# Power.net
KiCad netlist of a schematic drawn in Altium Designer
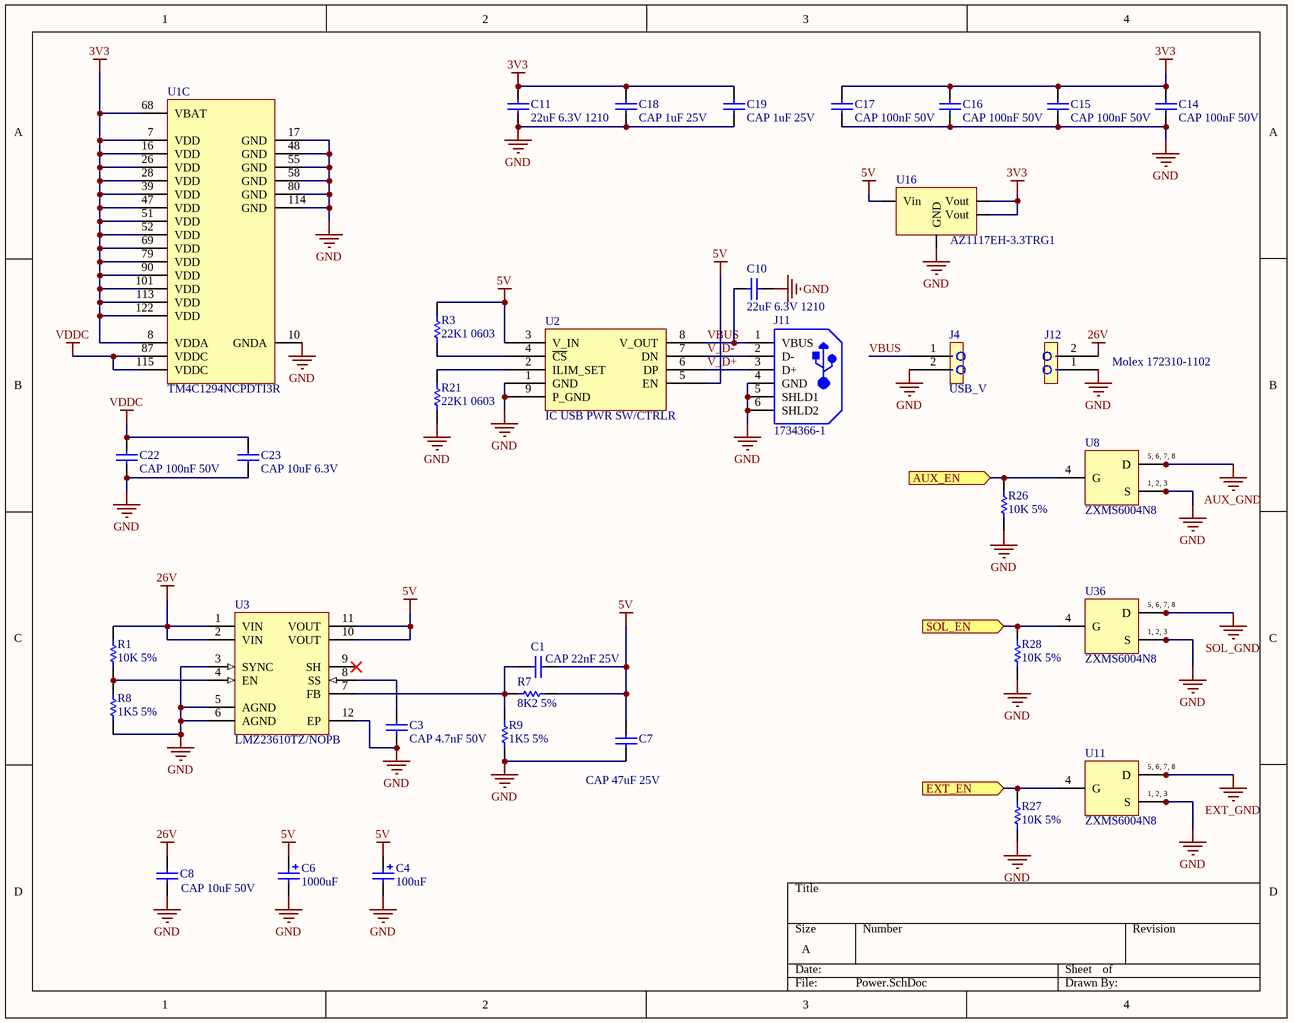
[diagram p0: Power.SchDoc]

(export (version "E")
  (design (tool "Eeschema 10.0.6"))
  (components
    (comp (ref "C1")
      (value "CAP 22nF 25V")
      (footprint "CAPC0805(2012)100_M")
      (description "CAP 22nF 25V Â±5% 0805 (2012 Metric) Thickness 1mm SMD")
      (fields (field (name "TOLERANCE") "Â±5%"))
      (libsource (lib "Altium Content Vault") (part "CMP-1036-04051-1"))
    )
    (comp (ref "C3")
      (value "CAP 4.7nF 50V")
      (footprint "CAPC0603(1608)100_M")
      (description "CAP 4.7nF 50V Â±20% 0603 (1608 Metric) Thickness 1mm SMD")
      (fields (field (name "TOLERANCE") "Â±20%"))
      (libsource (lib "Altium Content Vault") (part "CMP-1035-00333-1"))
    )
    (comp (ref "C4")
      (value "100uF")
      (footprint "PANASONIC_C")
      (description "Polarized Capacitor (Surface Mount)")
      (fields (field (name "PUBLISHER") "Altium Limited"))
      (libsource (lib "snarc+") (part "Cap_Polarized_100uF"))
    )
    (comp (ref "C6")
      (value "1000uF")
      (footprint "PANASONIC_H13")
      (description "Polarized Capacitor (Surface Mount)")
      (fields (field (name "PUBLISHER") "Altium Limited"))
      (libsource (lib "snarc+") (part "Cap_Polarized_1000uF"))
    )
    (comp (ref "C7")
      (value "CAP 47uF 25V")
      (footprint "CAPC1206(3216)100_L")
      (description "CAP 47uF 25V Â±0.25pF 1206 (3216 Metric) Thickness 1mm SMD")
      (fields (field (name "TOLERANCE") "Â±0.25pF"))
      (libsource (lib "Altium Content Vault") (part "CMP-1037-00376-1"))
    )
    (comp (ref "C8")
      (value "CAP 10uF 50V")
      (footprint "CAPC1206(3216)190_M")
      (description "CAP 10uF 50V Â±10% 1206 (3216 Metric) Thickness 1.9mm SMD")
      (fields (field (name "TOLERANCE") "Â±10%"))
      (libsource (lib "Altium Content Vault") (part "CMP-1037-04982-1"))
    )
    (comp (ref "C10")
      (value "22uF 6.3V 1210")
      (footprint "CAPC1210(3225)220_N")
      (description "CAP 22uF 6.3V ±10% 1210 (3225 Metric) Thickness 2.2mm SMD")
      (fields (field (name "TOLERANCE") "Â±10%"))
      (libsource (lib "Altium Content Vault") (part "CAP"))
    )
    (comp (ref "C11")
      (value "22uF 6.3V 1210")
      (footprint "CAPC1210(3225)220_N")
      (description "CAP 22uF 6.3V ±10% 1210 (3225 Metric) Thickness 2.2mm SMD")
      (fields (field (name "TOLERANCE") "Â±10%"))
      (libsource (lib "Altium Content Vault") (part "CAP"))
    )
    (comp (ref "C14")
      (value "CAP 100nF 50V")
      (footprint "CAPC0603(1608)100_M")
      (description "CAP 100nF 50V Â±0.1pF 0603 (1608 Metric) Thickness 1mm SMD")
      (fields (field (name "TOLERANCE") "Â±0.1pF"))
      (libsource (lib "Altium Content Vault") (part "CMP-1035-00010-1"))
    )
    (comp (ref "C15")
      (value "CAP 100nF 50V")
      (footprint "CAPC0603(1608)100_M")
      (description "CAP 100nF 50V Â±0.1pF 0603 (1608 Metric) Thickness 1mm SMD")
      (fields (field (name "TOLERANCE") "Â±0.1pF"))
      (libsource (lib "Altium Content Vault") (part "CMP-1035-00010-1"))
    )
    (comp (ref "C16")
      (value "CAP 100nF 50V")
      (footprint "CAPC0603(1608)100_M")
      (description "CAP 100nF 50V Â±0.1pF 0603 (1608 Metric) Thickness 1mm SMD")
      (fields (field (name "TOLERANCE") "Â±0.1pF"))
      (libsource (lib "Altium Content Vault") (part "CMP-1035-00010-1"))
    )
    (comp (ref "C17")
      (value "CAP 100nF 50V")
      (footprint "CAPC0603(1608)100_M")
      (description "CAP 100nF 50V Â±0.1pF 0603 (1608 Metric) Thickness 1mm SMD")
      (fields (field (name "TOLERANCE") "Â±0.1pF"))
      (libsource (lib "Altium Content Vault") (part "CMP-1035-00010-1"))
    )
    (comp (ref "C18")
      (value "CAP 1uF 25V")
      (footprint "CAPC0603(1608)100_M")
      (description "CAP 1uF 25V Â±0.25pF 0603 (1608 Metric) Thickness 1mm SMD")
      (fields (field (name "TOLERANCE") "Â±0.25pF"))
      (libsource (lib "Altium Content Vault") (part "CMP-1035-00037-1"))
    )
    (comp (ref "C19")
      (value "CAP 1uF 25V")
      (footprint "CAPC0603(1608)100_M")
      (description "CAP 1uF 25V Â±0.25pF 0603 (1608 Metric) Thickness 1mm SMD")
      (fields (field (name "TOLERANCE") "Â±0.25pF"))
      (libsource (lib "Altium Content Vault") (part "CMP-1035-00037-1"))
    )
    (comp (ref "C22")
      (value "CAP 100nF 50V")
      (footprint "CAPC0603(1608)100_M")
      (description "CAP 100nF 50V Â±0.1pF 0603 (1608 Metric) Thickness 1mm SMD")
      (fields (field (name "TOLERANCE") "Â±0.1pF"))
      (libsource (lib "Altium Content Vault") (part "CMP-1035-00010-1"))
    )
    (comp (ref "C23")
      (value "CAP 10uF 6.3V")
      (footprint "CAPC0603(1608)100_M")
      (description "CAP 10uF 6.3V ±10% 0603 (1608 Metric) Thickness 1mm SMD")
      (fields (field (name "TOLERANCE") "Â±10%"))
      (libsource (lib "Altium Content Vault") (part "CMP-1035-02796-1"))
    )
    (comp (ref "J4")
      (value "USB_V")
      (footprint "1X2")
      (description "6.35mm right-angle 90° male spade terminal PCB mount")
      (libsource (lib "") (part "CON2_1"))
    )
    (comp (ref "J11")
      (value "1734366-1")
      (footprint "TE-1734366-1_V")
      (description "Recept Assy, Vertical, 4 Position, Thru-Hole, Type A USB, RoHS, Tray")
      (libsource (lib "Altium Content Vault") (part "USB-4-2SHLD"))
    )
    (comp (ref "J12")
      (value "Molex 172310-1102")
      (footprint "Molex 172310-1102")
      (description "6.35mm right-angle 90° male spade terminal PCB mount")
      (libsource (lib "HSBNE-Vend") (part "CON2"))
    )
    (comp (ref "R1")
      (value "10K 5%")
      (footprint "RESC0603(1608)_M")
      (description "10K 0.1W 5% 0603 (1608 Metric)  SMD")
      (fields (field (name "TOLERANCE") "5 %") (field (name "POWER") "0.1 W"))
      (libsource (lib "Altium Content Vault") (part "CMP-1012-00098-1"))
    )
    (comp (ref "R3")
      (value "22K1 0603")
      (footprint "RESC0603(1608)_N")
      (description "22K1 0.1W 1% 0603 (1608 Metric)  SMD")
      (fields (field (name "TOLERANCE") "1 %") (field (name "POWER") "0.1 W"))
      (libsource (lib "Altium Content Vault") (part "RES"))
    )
    (comp (ref "R7")
      (value "8K2 5%")
      (footprint "RESC0603(1608)_M")
      (description "8K2 0.1W 5% 0603 (1608 Metric)  SMD")
      (fields (field (name "TOLERANCE") "5 %") (field (name "POWER") "0.1 W"))
      (libsource (lib "Altium Content Vault") (part "CMP-1012-00096-1"))
    )
    (comp (ref "R8")
      (value "1K5 5%")
      (footprint "RESC0603(1608)_M")
      (description "1K5 0.1W 5% 0603 (1608 Metric)  SMD")
      (fields (field (name "POWER") "0.1 W") (field (name "TOLERANCE") "5 %"))
      (libsource (lib "Altium Content Vault") (part "CMP-1012-00078-1"))
    )
    (comp (ref "R9")
      (value "1K5 5%")
      (footprint "RESC0603(1608)_M")
      (description "1K5 0.1W 5% 0603 (1608 Metric)  SMD")
      (fields (field (name "POWER") "0.1 W") (field (name "TOLERANCE") "5 %"))
      (libsource (lib "Altium Content Vault") (part "CMP-1012-00078-1"))
    )
    (comp (ref "R21")
      (value "22K1 0603")
      (footprint "RESC0603(1608)_N")
      (description "22K1 0.1W 1% 0603 (1608 Metric)  SMD")
      (fields (field (name "TOLERANCE") "1 %") (field (name "POWER") "0.1 W"))
      (libsource (lib "Altium Content Vault") (part "RES"))
    )
    (comp (ref "R26")
      (value "10K 5%")
      (footprint "RESC0603(1608)_N")
      (description "10K 0.1W 5% 0603 (1608 Metric)  SMD")
      (fields (field (name "TOLERANCE") "5 %") (field (name "POWER") "0.1 W"))
      (libsource (lib "Altium Content Vault") (part "RES"))
    )
    (comp (ref "R27")
      (value "10K 5%")
      (footprint "RESC0603(1608)_N")
      (description "10K 0.1W 5% 0603 (1608 Metric)  SMD")
      (fields (field (name "TOLERANCE") "5 %") (field (name "POWER") "0.1 W"))
      (libsource (lib "Altium Content Vault") (part "RES"))
    )
    (comp (ref "R28")
      (value "10K 5%")
      (footprint "RESC0603(1608)_N")
      (description "10K 0.1W 5% 0603 (1608 Metric)  SMD")
      (fields (field (name "TOLERANCE") "5 %") (field (name "POWER") "0.1 W"))
      (libsource (lib "Altium Content Vault") (part "RES"))
    )
    (comp (ref "U1")
      (value "TM4C1294NCPDTI3R")
      (footprint "TI-PDT128_M")
      (fields (field (name "MANUFACTURER") "Texas Instruments"))
      (libsource (lib "Altium Inc") (part "TI-TM4C1294NCPDT-128"))
    )
    (comp (ref "U2")
      (value "IC USB PWR SW/CTRLR")
      (footprint "8-MSOP-PowerPad")
      (description "USB Dedicated Charging Port, Power Switch")
      (libsource (lib "HSBNE-Vend") (part "IC USB PWR SW/CTRLR"))
    )
    (comp (ref "U3")
      (value "LMZ23610TZ/NOPB")
      (footprint "NDY0011A_M")
      (fields (field (name "MANUFACTURER") "Texas Instruments"))
      (libsource (lib "Altium Content Vault") (part "PM-REG-LMZ23610-12"))
    )
    (comp (ref "U8")
      (value "ZXMS6004N8")
      (footprint "SO-8")
      (description "MOSFET N-CH 60V 1.3A S08")
      (fields (field (name "MANUFACTURER") "On Semiconductor") (field (name "PARTNUMBER") "NCV8402ASTT1G"))
      (libsource (lib "HSBNE-MAIN") (part "ZXMS6004N8"))
    )
    (comp (ref "U11")
      (value "ZXMS6004N8")
      (footprint "SO-8")
      (description "MOSFET N-CH 60V 1.3A S08")
      (fields (field (name "MANUFACTURER") "On Semiconductor") (field (name "PARTNUMBER") "NCV8402ASTT1G"))
      (libsource (lib "HSBNE-MAIN") (part "ZXMS6004N8"))
    )
    (comp (ref "U16")
      (value "AZ1117EH-3.3TRG1")
      (footprint "SOT-223")
      (description "Reg 1A 3V3 OUT SIP VERT")
      (libsource (lib "HSBNE-Vend") (part "AZ1117EH"))
    )
    (comp (ref "U36")
      (value "ZXMS6004N8")
      (footprint "SO-8")
      (description "MOSFET N-CH 60V 1.3A S08")
      (fields (field (name "MANUFACTURER") "On Semiconductor") (field (name "PARTNUMBER") "NCV8402ASTT1G"))
      (libsource (lib "HSBNE-MAIN") (part "ZXMS6004N8"))
    )
  )
  (nets
    (net (code "1") (name "/AUX_EN") (class "Default")
      (node (ref "R26") (pin "2") (pinfunction "2_2") (pintype "passive"))
      (node (ref "U8") (pin "4") (pinfunction "G_4") (pintype "passive"))
    )
    (net (code "2") (name "/EXT_EN") (class "Default")
      (node (ref "R27") (pin "2") (pinfunction "2_2") (pintype "passive"))
      (node (ref "U11") (pin "4") (pinfunction "G_4") (pintype "passive"))
    )
    (net (code "3") (name "/SOL_EN") (class "Default")
      (node (ref "R28") (pin "2") (pinfunction "2_2") (pintype "passive"))
      (node (ref "U36") (pin "4") (pinfunction "G_4") (pintype "passive"))
    )
    (net (code "4") (name "/VBUS") (class "Default")
      (node (ref "C10") (pin "1") (pinfunction "1_1") (pintype "passive"))
      (node (ref "J11") (pin "1") (pinfunction "VBUS_1") (pintype "passive"))
      (node (ref "J4") (pin "1") (pintype "passive"))
      (node (ref "U2") (pin "8") (pinfunction "V_OUT_8") (pintype "power_in"))
    )
    (net (code "5") (name "/V_D+") (class "Default")
      (node (ref "J11") (pin "3") (pinfunction "D+_3") (pintype "passive"))
      (node (ref "U2") (pin "6") (pinfunction "DP_6") (pintype "power_in"))
    )
    (net (code "6") (name "/V_D-") (class "Default")
      (node (ref "J11") (pin "2") (pinfunction "D-_2") (pintype "passive"))
      (node (ref "U2") (pin "7") (pinfunction "DN_7") (pintype "power_in"))
    )
    (net (code "7") (name "3V3") (class "Default")
      (node (ref "C11") (pin "2") (pinfunction "2_2") (pintype "passive"))
      (node (ref "C14") (pin "2") (pinfunction "2_2") (pintype "passive"))
      (node (ref "C15") (pin "2") (pinfunction "2_2") (pintype "passive"))
      (node (ref "C16") (pin "2") (pinfunction "2_2") (pintype "passive"))
      (node (ref "C17") (pin "2") (pinfunction "2_2") (pintype "passive"))
      (node (ref "C18") (pin "2") (pinfunction "2_2") (pintype "passive"))
      (node (ref "C19") (pin "2") (pinfunction "2_2") (pintype "passive"))
      (node (ref "U1") (pin "101") (pinfunction "VDD_101") (pintype "power_in"))
      (node (ref "U1") (pin "113") (pinfunction "VDD_113") (pintype "power_in"))
      (node (ref "U1") (pin "122") (pinfunction "VDD_122") (pintype "power_in"))
      (node (ref "U1") (pin "16") (pinfunction "VDD_16") (pintype "power_in"))
      (node (ref "U1") (pin "26") (pinfunction "VDD_26") (pintype "power_in"))
      (node (ref "U1") (pin "28") (pinfunction "VDD_28") (pintype "power_in"))
      (node (ref "U1") (pin "39") (pinfunction "VDD_39") (pintype "power_in"))
      (node (ref "U1") (pin "47") (pinfunction "VDD_47") (pintype "power_in"))
      (node (ref "U1") (pin "51") (pinfunction "VDD_51") (pintype "power_in"))
      (node (ref "U1") (pin "52") (pinfunction "VDD_52") (pintype "power_in"))
      (node (ref "U1") (pin "68") (pinfunction "VBAT_68") (pintype "power_in"))
      (node (ref "U1") (pin "69") (pinfunction "VDD_69") (pintype "power_in"))
      (node (ref "U1") (pin "7") (pinfunction "VDD_7") (pintype "power_in"))
      (node (ref "U1") (pin "79") (pinfunction "VDD_79") (pintype "power_in"))
      (node (ref "U1") (pin "8") (pinfunction "VDDA_8") (pintype "power_in"))
      (node (ref "U1") (pin "90") (pinfunction "VDD_90") (pintype "power_in"))
      (node (ref "U16") (pin "2") (pinfunction "Vout_2") (pintype "power_in"))
      (node (ref "U16") (pin "4") (pinfunction "Vout_4") (pintype "power_in"))
    )
    (net (code "8") (name "5V") (class "Default")
      (node (ref "C1") (pin "2") (pinfunction "2_2") (pintype "passive"))
      (node (ref "C4") (pin "+") (pinfunction "+_+") (pintype "passive"))
      (node (ref "C6") (pin "+") (pinfunction "+_+") (pintype "passive"))
      (node (ref "C7") (pin "1") (pinfunction "1_1") (pintype "passive"))
      (node (ref "R3") (pin "1") (pinfunction "1_1") (pintype "passive"))
      (node (ref "R7") (pin "1") (pinfunction "1_1") (pintype "passive"))
      (node (ref "U16") (pin "3") (pinfunction "Vin_3") (pintype "power_in"))
      (node (ref "U2") (pin "3") (pinfunction "V_IN_3") (pintype "power_in"))
      (node (ref "U2") (pin "5") (pinfunction "EN_5") (pintype "power_in"))
      (node (ref "U3") (pin "10") (pinfunction "VOUT_10") (pintype "power_in"))
      (node (ref "U3") (pin "11") (pinfunction "VOUT_11") (pintype "power_in"))
    )
    (net (code "9") (name "26V") (class "Default")
      (node (ref "C8") (pin "1") (pinfunction "1_1") (pintype "passive"))
      (node (ref "J12") (pin "2") (pintype "passive"))
      (node (ref "R1") (pin "2") (pinfunction "2_2") (pintype "passive"))
      (node (ref "U3") (pin "1") (pinfunction "VIN_1") (pintype "power_in"))
      (node (ref "U3") (pin "2") (pinfunction "VIN_2") (pintype "power_in"))
    )
    (net (code "10") (name "AUX_GND") (class "Default")
      (node (ref "U8") (pin "5") (pinfunction "D_5") (pintype "passive"))
      (node (ref "U8") (pin "6") (pinfunction "D_6") (pintype "passive"))
      (node (ref "U8") (pin "7") (pinfunction "D_7") (pintype "passive"))
      (node (ref "U8") (pin "8") (pinfunction "D_8") (pintype "passive"))
    )
    (net (code "11") (name "EXT_GND") (class "Default")
      (node (ref "U11") (pin "5") (pinfunction "D_5") (pintype "passive"))
      (node (ref "U11") (pin "6") (pinfunction "D_6") (pintype "passive"))
      (node (ref "U11") (pin "7") (pinfunction "D_7") (pintype "passive"))
      (node (ref "U11") (pin "8") (pinfunction "D_8") (pintype "passive"))
    )
    (net (code "12") (name "GND") (class "Default")
      (node (ref "C10") (pin "2") (pinfunction "2_2") (pintype "passive"))
      (node (ref "C11") (pin "1") (pinfunction "1_1") (pintype "passive"))
      (node (ref "C14") (pin "1") (pinfunction "1_1") (pintype "passive"))
      (node (ref "C15") (pin "1") (pinfunction "1_1") (pintype "passive"))
      (node (ref "C16") (pin "1") (pinfunction "1_1") (pintype "passive"))
      (node (ref "C17") (pin "1") (pinfunction "1_1") (pintype "passive"))
      (node (ref "C18") (pin "1") (pinfunction "1_1") (pintype "passive"))
      (node (ref "C19") (pin "1") (pinfunction "1_1") (pintype "passive"))
      (node (ref "C22") (pin "1") (pinfunction "1_1") (pintype "passive"))
      (node (ref "C23") (pin "1") (pinfunction "1_1") (pintype "passive"))
      (node (ref "C3") (pin "1") (pinfunction "1_1") (pintype "passive"))
      (node (ref "C4") (pin "-") (pinfunction "-_-") (pintype "passive"))
      (node (ref "C6") (pin "-") (pinfunction "-_-") (pintype "passive"))
      (node (ref "C7") (pin "2") (pinfunction "2_2") (pintype "passive"))
      (node (ref "C8") (pin "2") (pinfunction "2_2") (pintype "passive"))
      (node (ref "J11") (pin "4") (pinfunction "GND_4") (pintype "passive"))
      (node (ref "J11") (pin "5") (pinfunction "SHLD1_5") (pintype "passive"))
      (node (ref "J11") (pin "6") (pinfunction "SHLD2_6") (pintype "passive"))
      (node (ref "J12") (pin "1") (pintype "passive"))
      (node (ref "J4") (pin "2") (pintype "passive"))
      (node (ref "R21") (pin "1") (pinfunction "1_1") (pintype "passive"))
      (node (ref "R26") (pin "1") (pinfunction "1_1") (pintype "passive"))
      (node (ref "R27") (pin "1") (pinfunction "1_1") (pintype "passive"))
      (node (ref "R28") (pin "1") (pinfunction "1_1") (pintype "passive"))
      (node (ref "R8") (pin "1") (pinfunction "1_1") (pintype "passive"))
      (node (ref "R9") (pin "1") (pinfunction "1_1") (pintype "passive"))
      (node (ref "U1") (pin "10") (pinfunction "GNDA_10") (pintype "power_in"))
      (node (ref "U1") (pin "114") (pinfunction "GND_114") (pintype "power_in"))
      (node (ref "U1") (pin "17") (pinfunction "GND_17") (pintype "power_in"))
      (node (ref "U1") (pin "48") (pinfunction "GND_48") (pintype "power_in"))
      (node (ref "U1") (pin "55") (pinfunction "GND_55") (pintype "power_in"))
      (node (ref "U1") (pin "58") (pinfunction "GND_58") (pintype "power_in"))
      (node (ref "U1") (pin "80") (pinfunction "GND_80") (pintype "power_in"))
      (node (ref "U11") (pin "1") (pinfunction "S_1") (pintype "passive"))
      (node (ref "U11") (pin "2") (pinfunction "S_2") (pintype "passive"))
      (node (ref "U11") (pin "3") (pinfunction "S_3") (pintype "passive"))
      (node (ref "U16") (pin "1") (pinfunction "GND_1") (pintype "power_in"))
      (node (ref "U2") (pin "1") (pinfunction "GND_1") (pintype "passive"))
      (node (ref "U2") (pin "9") (pinfunction "P_GND_9") (pintype "power_in"))
      (node (ref "U3") (pin "12") (pinfunction "EP_12") (pintype "power_in"))
      (node (ref "U3") (pin "3") (pinfunction "SYNC_3") (pintype "input"))
      (node (ref "U3") (pin "5") (pinfunction "AGND_5") (pintype "power_in"))
      (node (ref "U3") (pin "6") (pinfunction "AGND_6") (pintype "power_in"))
      (node (ref "U36") (pin "1") (pinfunction "S_1") (pintype "passive"))
      (node (ref "U36") (pin "2") (pinfunction "S_2") (pintype "passive"))
      (node (ref "U36") (pin "3") (pinfunction "S_3") (pintype "passive"))
      (node (ref "U8") (pin "1") (pinfunction "S_1") (pintype "passive"))
      (node (ref "U8") (pin "2") (pinfunction "S_2") (pintype "passive"))
      (node (ref "U8") (pin "3") (pinfunction "S_3") (pintype "passive"))
    )
    (net (code "13") (name "Net-(U2-ILIM_SET)") (class "Default")
      (node (ref "R21") (pin "2") (pinfunction "2_2") (pintype "passive"))
      (node (ref "U2") (pin "2") (pinfunction "ILIM_SET_2") (pintype "passive"))
    )
    (net (code "14") (name "Net-(U2-~{CS})") (class "Default")
      (node (ref "R3") (pin "2") (pinfunction "2_2") (pintype "passive"))
      (node (ref "U2") (pin "4") (pinfunction "~{CS}_4") (pintype "power_in"))
    )
    (net (code "15") (name "Net-(U3-EN)") (class "Default")
      (node (ref "R1") (pin "1") (pinfunction "1_1") (pintype "passive"))
      (node (ref "R8") (pin "2") (pinfunction "2_2") (pintype "passive"))
      (node (ref "U3") (pin "4") (pinfunction "EN_4") (pintype "input"))
    )
    (net (code "16") (name "Net-(U3-FB)") (class "Default")
      (node (ref "C1") (pin "1") (pinfunction "1_1") (pintype "passive"))
      (node (ref "R7") (pin "2") (pinfunction "2_2") (pintype "passive"))
      (node (ref "R9") (pin "2") (pinfunction "2_2") (pintype "passive"))
      (node (ref "U3") (pin "7") (pinfunction "FB_7") (pintype "passive"))
    )
    (net (code "17") (name "Net-(U3-SS)") (class "Default")
      (node (ref "C3") (pin "2") (pinfunction "2_2") (pintype "passive"))
      (node (ref "U3") (pin "8") (pinfunction "SS_8") (pintype "input"))
    )
    (net (code "18") (name "SOL_GND") (class "Default")
      (node (ref "U36") (pin "5") (pinfunction "D_5") (pintype "passive"))
      (node (ref "U36") (pin "6") (pinfunction "D_6") (pintype "passive"))
      (node (ref "U36") (pin "7") (pinfunction "D_7") (pintype "passive"))
      (node (ref "U36") (pin "8") (pinfunction "D_8") (pintype "passive"))
    )
    (net (code "19") (name "VDDC") (class "Default")
      (node (ref "C22") (pin "2") (pinfunction "2_2") (pintype "passive"))
      (node (ref "C23") (pin "2") (pinfunction "2_2") (pintype "passive"))
      (node (ref "U1") (pin "115") (pinfunction "VDDC_115") (pintype "power_in"))
      (node (ref "U1") (pin "87") (pinfunction "VDDC_87") (pintype "power_in"))
    )
    (net (code "20") (name "unconnected-(U3-SH-Pad9)") (class "Default")
      (node (ref "U3") (pin "9") (pinfunction "SH_9") (pintype "passive+no_connect"))
    )
  )
)
